# SENSORS_FMU3_REV_G.net
KiCad netlist of a schematic drawn in Altium Designer
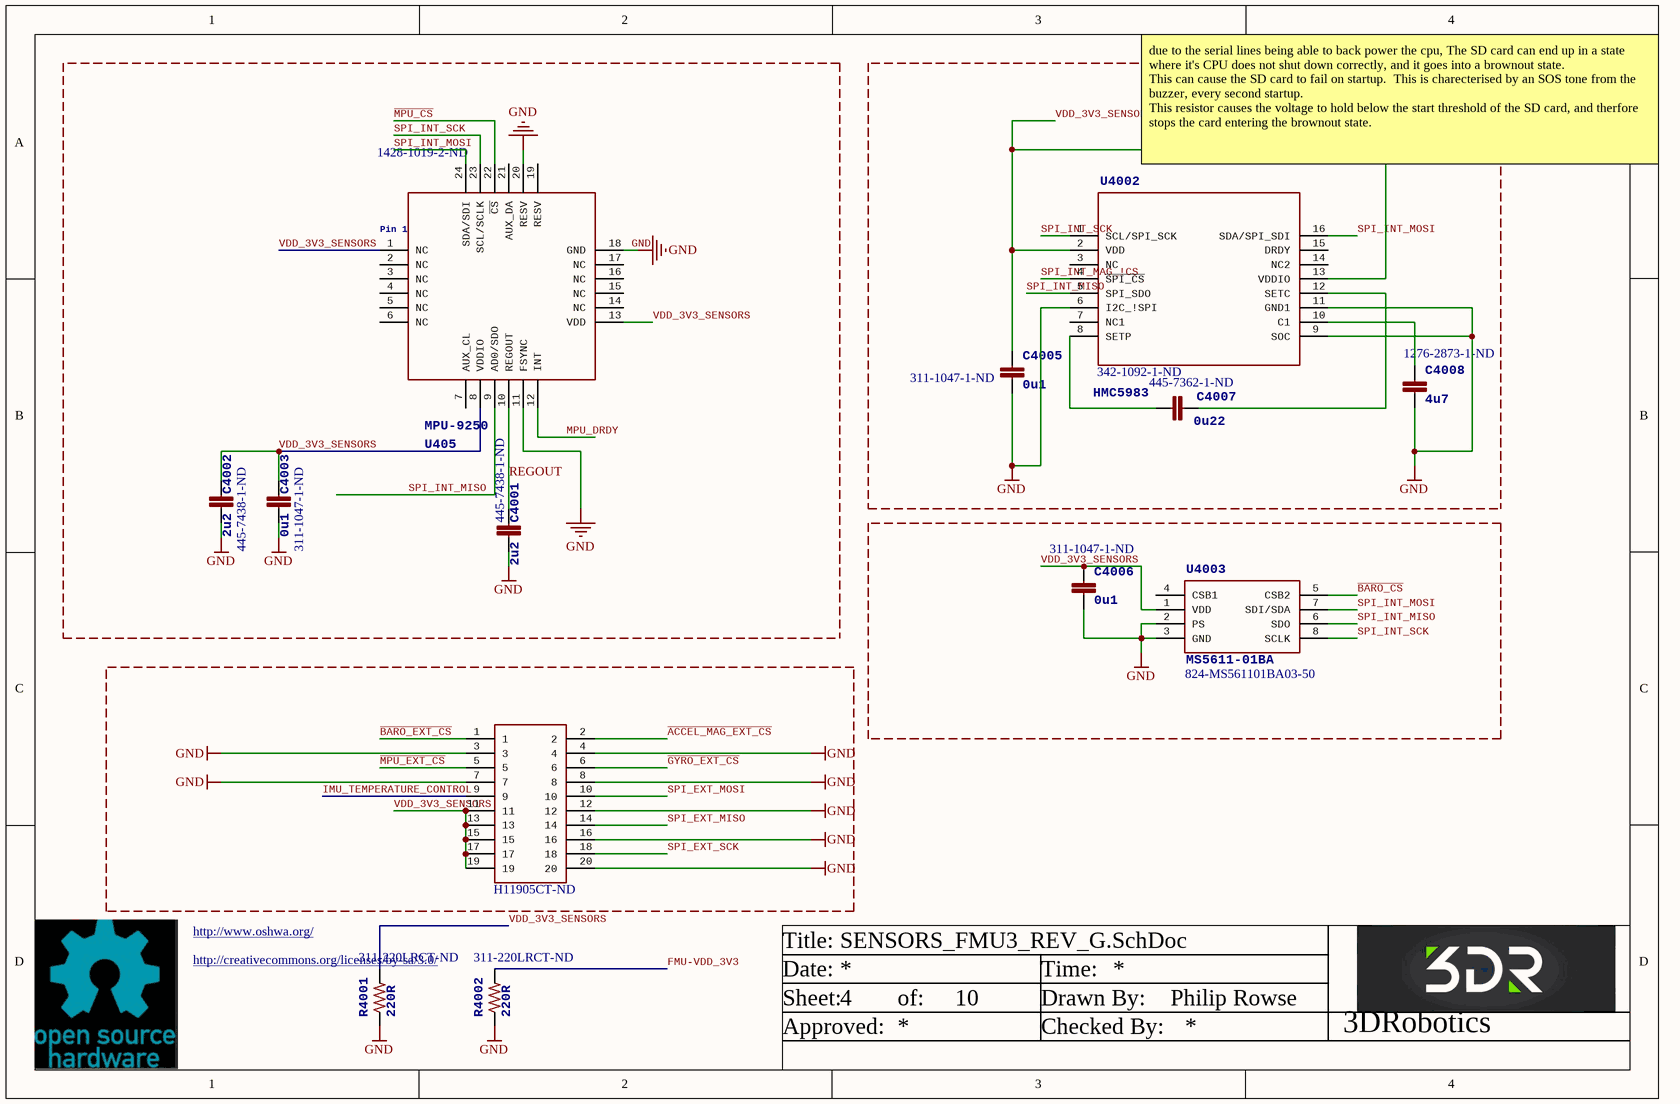
[diagram p0: SENSORS_FMU3_REV_G.SchDoc]

(export (version "E")
  (design (tool "Eeschema 10.0.6"))
  (components
    (comp (ref "C4001")
      (value "2u2")
      (footprint "0603-CAP")
      (description "CAP CER 2.2UF 16V 10% X6S 0603")
      (fields
        (field (name "PARTNO") "C1608X6S1C225K080AC")
        (field (name "SUPPLIER PART NUMBER 1") "445-7438-1-ND")
        (field (name "3DR_PARTNO") "ECM0619")
      )
      (libsource (lib "pixhawk2") (part "CAP0603"))
    )
    (comp (ref "C4002")
      (value "2u2")
      (footprint "0603-CAP")
      (description "CAP CER 2.2UF 16V 10% X6S 0603")
      (fields
        (field (name "PARTNO") "C1608X6S1C225K080AC")
        (field (name "SUPPLIER PART NUMBER 1") "445-7438-1-ND")
        (field (name "3DR_PARTNO") "ECM0619")
      )
      (libsource (lib "pixhawk2") (part "CAP0603"))
    )
    (comp (ref "C4003")
      (value "0u1")
      (footprint "0402-CAP")
      (description "CAP CER 0.1UF 16V Y5V 0402")
      (fields
        (field (name "PARTNO") "CC0402ZRY5V7BB104")
        (field (name "SUPPLIER PART NUMBER 1") "311-1047-1-ND")
        (field (name "3DR_PARTNO") "ECM0700")
      )
      (libsource (lib "") (part "CAP0402_1"))
    )
    (comp (ref "C4005")
      (value "0u1")
      (footprint "0402-CAP")
      (description "CAP CER 0.1UF 16V Y5V 0402")
      (fields
        (field (name "SUPPLIER PART NUMBER 1") "311-1047-1-ND")
        (field (name "3DR_PARTNO") "ECM0700")
        (field (name "PARTNO") "CC0402ZRY5V7BB104")
      )
      (libsource (lib "") (part "CAP0402_1"))
    )
    (comp (ref "C4006")
      (value "0u1")
      (footprint "0402-CAP")
      (description "CAP CER 0.1UF 16V Y5V 0402")
      (fields
        (field (name "PARTNO") "CC0402ZRY5V7BB104")
        (field (name "SUPPLIER PART NUMBER 1") "311-1047-1-ND")
        (field (name "3DR_PARTNO") "ECM0700")
      )
      (libsource (lib "") (part "CAP0402_1"))
    )
    (comp (ref "C4007")
      (value "0u22")
      (footprint "0402-CAP")
      (description "CAP CER 0.22UF 25V 10% X7R 0402")
      (fields
        (field (name "3DR_PARTNO") "ECM")
        (field (name "PARTNO") "C1005X6S1E224K050BC")
        (field (name "SUPPLIER PART NUMBER 1") "445-7362-1-ND")
      )
      (libsource (lib "pixhawk2") (part "CAP0402"))
    )
    (comp (ref "C4008")
      (value "4u7")
      (footprint "0805")
      (description "CAP CER 4.7UF 16V 10% X7R 0805")
      (fields
        (field (name "PARTNO") "CL21B475KOFNNNE")
        (field (name "SUPPLIER PART NUMBER 1") "1276-2873-1-ND")
        (field (name "3DR_PARTNO") "ECM0622")
      )
      (libsource (lib "pixhawk2") (part "CAP0805"))
    )
    (comp (ref "R4001")
      (value "220R")
      (footprint "0402-RES")
      (description "RES 220 OHM 1/16W 1% 0402 SMD")
      (fields
        (field (name "SUPPLIER PART NUMBER 1") "311-220LRCT-ND")
        (field (name "3DR_PARTNO") "ECM0821")
        (field (name "PARTNO") "RC0402FR-07220RL")
      )
      (libsource (lib "pixhawk2") (part "RESISTOR0402-RES"))
    )
    (comp (ref "R4002")
      (value "220R")
      (footprint "0402-RES")
      (description "RES 220 OHM 1/16W 1% 0402 SMD")
      (fields
        (field (name "SUPPLIER PART NUMBER 1") "311-220LRCT-ND")
        (field (name "3DR_PARTNO") "ECM0821")
        (field (name "PARTNO") "RC0402FR-07220RL")
      )
      (libsource (lib "pixhawk2") (part "RESISTOR0402-RES"))
    )
    (comp (ref "U$2")
      (value "DF40C-20-DS")
      (footprint "DF-40C-20DS")
      (description "CONN RCPT 20POS 0.4MM SMD GOLD")
      (fields
        (field (name "SUPPLIER PART NUMBER 1") "H11905CT-ND")
        (field (name "3DR_PARTNO") "ECM0517")
        (field (name "PARTNO") "DF40C(2.0)-20DS-0.4V(51)")
      )
      (libsource (lib "pixhawk2") (part "DF40C-20-DS"))
    )
    (comp (ref "U405")
      (value "MPU-9250")
      (footprint "MPU-9250")
      (fields (field (name "PIN 1") "Pin 1") (field (name "SUPPLIER PART NUMBER 1") "1428-1019-2-ND"))
      (libsource (lib "pixhawk2") (part "MPU-6500"))
    )
    (comp (ref "U4002")
      (value "HMC5983")
      (footprint "HMC5983-new")
      (description "IC COMPASS 3 AXIS 16-LCC")
      (fields (field (name "SUPPLIER PART NUMBER 1") "342-1092-1-ND") (field (name "3DR_PARTNO") "ECM0672"))
      (libsource (lib "pixhawk2") (part "HMC5983"))
    )
    (comp (ref "U4003")
      (value "MS5611-01BA")
      (footprint "MS5611-01BA")
      (description "Board Mount Pressure Sensors")
      (fields
        (field (name "SUPPLIER PART NUMBER 1") "824-MS561101BA03-50")
        (field (name "3DR_PARTNO") "ECM0835")
      )
      (libsource (lib "pixhawk2") (part "MS5611-01BA"))
    )
  )
  (nets
    (net (code "1") (name "/FMU-VDD_3V3") (class "Default")
      (node (ref "R4002") (pin "P$2") (pinfunction "2_P$2") (pintype "passive"))
    )
    (net (code "2") (name "/IMU_TEMPERATURE_CONTROL") (class "Default")
      (node (ref "U$2") (pin "9") (pinfunction "9_9") (pintype "passive"))
    )
    (net (code "3") (name "/MPU_DRDY") (class "Default")
      (node (ref "U405") (pin "12") (pinfunction "INT_12") (pintype "passive"))
    )
    (net (code "4") (name "/REGOUT") (class "Default")
      (node (ref "C4001") (pin "P$1") (pinfunction "1_P$1") (pintype "passive"))
      (node (ref "U405") (pin "10") (pinfunction "REGOUT_10") (pintype "passive"))
    )
    (net (code "5") (name "/SPI_EXT_MISO") (class "Default")
      (node (ref "U$2") (pin "14") (pinfunction "14_14") (pintype "passive"))
    )
    (net (code "6") (name "/SPI_EXT_MOSI") (class "Default")
      (node (ref "U$2") (pin "10") (pinfunction "10_10") (pintype "passive"))
    )
    (net (code "7") (name "/SPI_EXT_SCK") (class "Default")
      (node (ref "U$2") (pin "18") (pinfunction "18_18") (pintype "passive"))
    )
    (net (code "8") (name "/SPI_INT_MAG_!CS") (class "Default")
      (node (ref "U4002") (pin "4") (pinfunction "~{SPI_CS}_4") (pintype "passive"))
    )
    (net (code "9") (name "/SPI_INT_MISO") (class "Default")
      (node (ref "U4002") (pin "5") (pinfunction "SPI_SDO_5") (pintype "passive"))
      (node (ref "U4003") (pin "6") (pinfunction "SDO_6") (pintype "passive"))
      (node (ref "U405") (pin "9") (pinfunction "AD0/SDO_9") (pintype "passive"))
    )
    (net (code "10") (name "/SPI_INT_MOSI") (class "Default")
      (node (ref "U4002") (pin "16") (pinfunction "SDA/SPI_SDI_16") (pintype "passive"))
      (node (ref "U4003") (pin "7") (pinfunction "SDI/SDA_7") (pintype "passive"))
      (node (ref "U405") (pin "24") (pinfunction "SDA/SDI_24") (pintype "passive"))
    )
    (net (code "11") (name "/SPI_INT_SCK") (class "Default")
      (node (ref "U4002") (pin "1") (pinfunction "SCL/SPI_SCK_1") (pintype "passive"))
      (node (ref "U4003") (pin "8") (pinfunction "SCLK_8") (pintype "passive"))
      (node (ref "U405") (pin "23") (pinfunction "SCL/SCLK_23") (pintype "passive"))
    )
    (net (code "12") (name "/VDD_3V3_SENSORS") (class "Default")
      (node (ref "C4002") (pin "P$1") (pinfunction "1_P$1") (pintype "passive"))
      (node (ref "C4003") (pin "P$1") (pinfunction "1_P$1") (pintype "passive"))
      (node (ref "C4005") (pin "P$1") (pinfunction "1_P$1") (pintype "passive"))
      (node (ref "C4006") (pin "P$1") (pinfunction "1_P$1") (pintype "passive"))
      (node (ref "R4001") (pin "P$2") (pinfunction "2_P$2") (pintype "passive"))
      (node (ref "U$2") (pin "11") (pinfunction "11_11") (pintype "passive"))
      (node (ref "U$2") (pin "13") (pinfunction "13_13") (pintype "passive"))
      (node (ref "U$2") (pin "15") (pinfunction "15_15") (pintype "passive"))
      (node (ref "U$2") (pin "17") (pinfunction "17_17") (pintype "passive"))
      (node (ref "U$2") (pin "19") (pinfunction "19_19") (pintype "passive"))
      (node (ref "U4002") (pin "13") (pinfunction "VDDIO_13") (pintype "power_in"))
      (node (ref "U4002") (pin "2") (pinfunction "VDD_2") (pintype "power_in"))
      (node (ref "U4003") (pin "1") (pinfunction "VDD_1") (pintype "passive"))
      (node (ref "U405") (pin "1") (pinfunction "NC_1") (pintype "passive"))
      (node (ref "U405") (pin "13") (pinfunction "VDD_13") (pintype "passive"))
      (node (ref "U405") (pin "8") (pinfunction "VDDIO_8") (pintype "passive"))
    )
    (net (code "13") (name "/~{ACCEL_MAG_EXT_CS}") (class "Default")
      (node (ref "U$2") (pin "2") (pinfunction "2_2") (pintype "passive"))
    )
    (net (code "14") (name "/~{BARO_CS}") (class "Default")
      (node (ref "U4003") (pin "5") (pinfunction "CSB2_5") (pintype "passive"))
    )
    (net (code "15") (name "/~{BARO_EXT_CS}") (class "Default")
      (node (ref "U$2") (pin "1") (pinfunction "1_1") (pintype "passive"))
    )
    (net (code "16") (name "/~{GYRO_EXT_CS}") (class "Default")
      (node (ref "U$2") (pin "6") (pinfunction "6_6") (pintype "passive"))
    )
    (net (code "17") (name "/~{MPU_CS}") (class "Default")
      (node (ref "U405") (pin "22") (pinfunction "~{CS}_22") (pintype "passive"))
    )
    (net (code "18") (name "/~{MPU_EXT_CS}") (class "Default")
      (node (ref "U$2") (pin "5") (pinfunction "5_5") (pintype "passive"))
    )
    (net (code "19") (name "GND") (class "Default")
      (node (ref "C4001") (pin "P$2") (pinfunction "2_P$2") (pintype "passive"))
      (node (ref "C4002") (pin "P$2") (pinfunction "2_P$2") (pintype "passive"))
      (node (ref "C4003") (pin "P$2") (pinfunction "2_P$2") (pintype "passive"))
      (node (ref "C4005") (pin "P$2") (pinfunction "2_P$2") (pintype "passive"))
      (node (ref "C4006") (pin "P$2") (pinfunction "2_P$2") (pintype "passive"))
      (node (ref "C4008") (pin "2") (pinfunction "2_2") (pintype "passive"))
      (node (ref "R4001") (pin "P$1") (pinfunction "1_P$1") (pintype "passive"))
      (node (ref "R4002") (pin "P$1") (pinfunction "1_P$1") (pintype "passive"))
      (node (ref "U$2") (pin "12") (pinfunction "12_12") (pintype "passive"))
      (node (ref "U$2") (pin "16") (pinfunction "16_16") (pintype "passive"))
      (node (ref "U$2") (pin "20") (pinfunction "20_20") (pintype "passive"))
      (node (ref "U$2") (pin "3") (pinfunction "3_3") (pintype "passive"))
      (node (ref "U$2") (pin "4") (pinfunction "4_4") (pintype "passive"))
      (node (ref "U$2") (pin "7") (pinfunction "7_7") (pintype "passive"))
      (node (ref "U$2") (pin "8") (pinfunction "8_8") (pintype "passive"))
      (node (ref "U4002") (pin "11") (pinfunction "GND1_11") (pintype "passive"))
      (node (ref "U4002") (pin "6") (pinfunction "I2C_!SPI_6") (pintype "passive"))
      (node (ref "U4002") (pin "9") (pinfunction "SOC_9") (pintype "passive"))
      (node (ref "U4003") (pin "2") (pinfunction "PS_2") (pintype "passive"))
      (node (ref "U4003") (pin "3") (pinfunction "GND_3") (pintype "passive"))
      (node (ref "U405") (pin "11") (pinfunction "FSYNC_11") (pintype "passive"))
      (node (ref "U405") (pin "18") (pinfunction "GND_18") (pintype "passive"))
      (node (ref "U405") (pin "20") (pinfunction "RESV_20") (pintype "passive"))
    )
    (net (code "20") (name "Net-(C4007-1)") (class "Default")
      (node (ref "C4007") (pin "P$1") (pinfunction "1_P$1") (pintype "passive"))
      (node (ref "U4002") (pin "12") (pinfunction "SETC_12") (pintype "passive"))
    )
    (net (code "21") (name "Net-(C4007-2)") (class "Default")
      (node (ref "C4007") (pin "P$2") (pinfunction "2_P$2") (pintype "passive"))
      (node (ref "U4002") (pin "8") (pinfunction "SETP_8") (pintype "passive"))
    )
    (net (code "22") (name "Net-(U4002-C1)") (class "Default")
      (node (ref "C4008") (pin "1") (pinfunction "1_1") (pintype "passive"))
      (node (ref "U4002") (pin "10") (pinfunction "C1_10") (pintype "passive"))
    )
    (net (code "23") (name "unconnected-(U405-AUX_CL-Pad7)") (class "Default")
      (node (ref "U405") (pin "7") (pinfunction "AUX_CL_7") (pintype "passive"))
    )
    (net (code "24") (name "unconnected-(U405-AUX_DA-Pad21)") (class "Default")
      (node (ref "U405") (pin "21") (pinfunction "AUX_DA_21") (pintype "passive"))
    )
    (net (code "25") (name "unconnected-(U405-NC-Pad2)") (class "Default")
      (node (ref "U405") (pin "2") (pinfunction "NC_2") (pintype "passive"))
    )
    (net (code "26") (name "unconnected-(U405-NC-Pad3)") (class "Default")
      (node (ref "U405") (pin "3") (pinfunction "NC_3") (pintype "passive"))
    )
    (net (code "27") (name "unconnected-(U405-NC-Pad4)") (class "Default")
      (node (ref "U405") (pin "4") (pinfunction "NC_4") (pintype "passive"))
    )
    (net (code "28") (name "unconnected-(U405-NC-Pad5)") (class "Default")
      (node (ref "U405") (pin "5") (pinfunction "NC_5") (pintype "passive"))
    )
    (net (code "29") (name "unconnected-(U405-NC-Pad6)") (class "Default")
      (node (ref "U405") (pin "6") (pinfunction "NC_6") (pintype "passive"))
    )
    (net (code "30") (name "unconnected-(U405-NC-Pad14)") (class "Default")
      (node (ref "U405") (pin "14") (pinfunction "NC_14") (pintype "passive"))
    )
    (net (code "31") (name "unconnected-(U405-NC-Pad15)") (class "Default")
      (node (ref "U405") (pin "15") (pinfunction "NC_15") (pintype "passive"))
    )
    (net (code "32") (name "unconnected-(U405-NC-Pad16)") (class "Default")
      (node (ref "U405") (pin "16") (pinfunction "NC_16") (pintype "passive"))
    )
    (net (code "33") (name "unconnected-(U405-NC-Pad17)") (class "Default")
      (node (ref "U405") (pin "17") (pinfunction "NC_17") (pintype "passive"))
    )
    (net (code "34") (name "unconnected-(U405-RESV-Pad19)") (class "Default")
      (node (ref "U405") (pin "19") (pinfunction "RESV_19") (pintype "passive"))
    )
    (net (code "35") (name "unconnected-(U4002-DRDY-Pad15)") (class "Default")
      (node (ref "U4002") (pin "15") (pinfunction "DRDY_15") (pintype "passive"))
    )
    (net (code "36") (name "unconnected-(U4002-NC-Pad3)") (class "Default")
      (node (ref "U4002") (pin "3") (pinfunction "NC_3") (pintype "passive"))
    )
    (net (code "37") (name "unconnected-(U4002-NC1-Pad7)") (class "Default")
      (node (ref "U4002") (pin "7") (pinfunction "NC1_7") (pintype "passive"))
    )
    (net (code "38") (name "unconnected-(U4002-NC2-Pad14)") (class "Default")
      (node (ref "U4002") (pin "14") (pinfunction "NC2_14") (pintype "passive"))
    )
    (net (code "39") (name "unconnected-(U4003-CSB1-Pad4)") (class "Default")
      (node (ref "U4003") (pin "4") (pinfunction "CSB1_4") (pintype "passive"))
    )
  )
)
